# -9V_Supply.net
KiCad netlist of a schematic drawn in Altium Designer
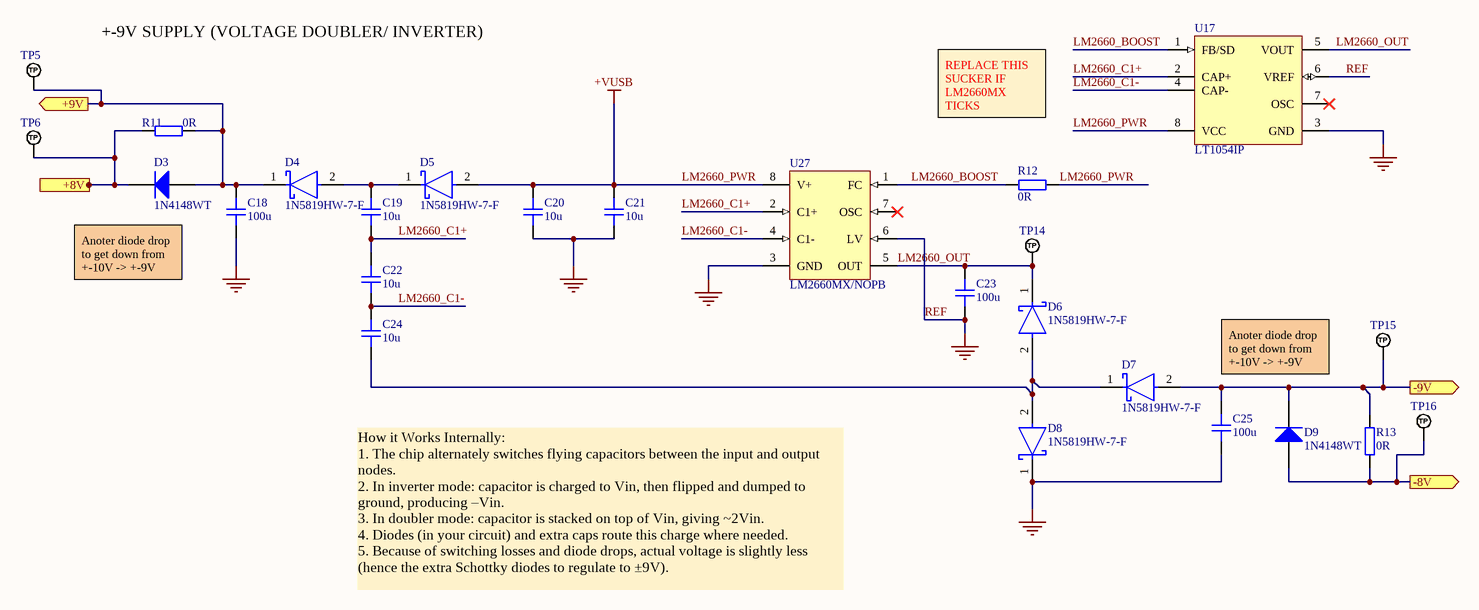
[diagram p0: +-9V Supply.SchDoc]

(export (version "E")
  (design (tool "Eeschema 10.0.6"))
  (components
    (comp (ref "C18")
      (value "100u")
      (footprint "CAP_1210")
      (description "Capacitor SMD 1210")
      (libsource (lib "Schematic-Lib-PhilsLab") (part "CAP_1210"))
    )
    (comp (ref "C19")
      (value "10u")
      (footprint "CAP_1210")
      (description "Capacitor SMD 1210")
      (libsource (lib "Schematic-Lib-PhilsLab") (part "CAP_1210"))
    )
    (comp (ref "C20")
      (value "10u")
      (footprint "CAP_1210")
      (description "Capacitor SMD 1210")
      (libsource (lib "Schematic-Lib-PhilsLab") (part "CAP_1210"))
    )
    (comp (ref "C21")
      (value "10u")
      (footprint "CAP_1210")
      (description "Capacitor SMD 1210")
      (libsource (lib "Schematic-Lib-PhilsLab") (part "CAP_1210"))
    )
    (comp (ref "C22")
      (value "10u")
      (footprint "CAP_1210")
      (description "Capacitor SMD 1210")
      (libsource (lib "Schematic-Lib-PhilsLab") (part "CAP_1210"))
    )
    (comp (ref "C23")
      (value "100u")
      (footprint "CAP_1210")
      (description "Capacitor SMD 1210")
      (libsource (lib "Schematic-Lib-PhilsLab") (part "CAP_1210"))
    )
    (comp (ref "C24")
      (value "10u")
      (footprint "CAP_1210")
      (description "Capacitor SMD 1210")
      (libsource (lib "Schematic-Lib-PhilsLab") (part "CAP_1210"))
    )
    (comp (ref "C25")
      (value "100u")
      (footprint "CAP_1210")
      (description "Capacitor SMD 1210")
      (libsource (lib "Schematic-Lib-PhilsLab") (part "CAP_1210"))
    )
    (comp (ref "D3")
      (value "1N4148WT")
      (footprint "FAIR-SOD-523F-2_V")
      (description "High Conductance Fast Switching Diode, 75 V, -55 to 150 degC, 2-Pin SOD523F, RoHS")
      (fields (field (name "MANUFACTURER") "Fairchild Semiconductor"))
      (libsource (lib "Altium Content Vault") (part "FAIR-D_K1A2-2"))
    )
    (comp (ref "D4")
      (value "1N5819HW-7-F")
      (footprint "FP-SOD123-IPC_A")
      (description "DIODE SCHOTTKY 40V 1A SOD123")
      (libsource (lib "Altium Content Vault") (part "1d6ec82d83fb6aee721767c19dac4b9"))
    )
    (comp (ref "D5")
      (value "1N5819HW-7-F")
      (footprint "FP-SOD123-IPC_A")
      (description "DIODE SCHOTTKY 40V 1A SOD123")
      (libsource (lib "Altium Content Vault") (part "1d6ec82d83fb6aee721767c19dac4b9"))
    )
    (comp (ref "D6")
      (value "1N5819HW-7-F")
      (footprint "FP-SOD123-IPC_A")
      (description "DIODE SCHOTTKY 40V 1A SOD123")
      (libsource (lib "Altium Content Vault") (part "1d6ec82d83fb6aee721767c19dac4b9"))
    )
    (comp (ref "D7")
      (value "1N5819HW-7-F")
      (footprint "FP-SOD123-IPC_A")
      (description "DIODE SCHOTTKY 40V 1A SOD123")
      (libsource (lib "Altium Content Vault") (part "1d6ec82d83fb6aee721767c19dac4b9"))
    )
    (comp (ref "D8")
      (value "1N5819HW-7-F")
      (footprint "FP-SOD123-IPC_A")
      (description "DIODE SCHOTTKY 40V 1A SOD123")
      (libsource (lib "Altium Content Vault") (part "1d6ec82d83fb6aee721767c19dac4b9"))
    )
    (comp (ref "D9")
      (value "1N4148WT")
      (footprint "FAIR-SOD-523F-2_V")
      (description "High Conductance Fast Switching Diode, 75 V, -55 to 150 degC, 2-Pin SOD523F, RoHS")
      (fields (field (name "MANUFACTURER") "Fairchild Semiconductor"))
      (libsource (lib "Altium Content Vault") (part "FAIR-D_K1A2-2"))
    )
    (comp (ref "R11")
      (value "0R")
      (footprint "RES_0603")
      (description "Resistor SMD 0603")
      (libsource (lib "Schematic-Lib-PhilsLab") (part "RES_0603"))
    )
    (comp (ref "R12")
      (value "0R")
      (footprint "RES_0603")
      (description "Resistor SMD 0603")
      (libsource (lib "Schematic-Lib-PhilsLab") (part "RES_0603"))
    )
    (comp (ref "R13")
      (value "0R")
      (footprint "RES_0603")
      (description "Resistor SMD 0603")
      (libsource (lib "Schematic-Lib-PhilsLab") (part "RES_0603"))
    )
    (comp (ref "TP5")
      (value "TP_NOBOM")
      (footprint "PAD_RND_1MM")
      (description "Test Point Round 1mm (NO BOM)")
      (libsource (lib "Schematic-Lib-PhilsLab") (part "TEST_POINT_RND_1MM"))
    )
    (comp (ref "TP6")
      (value "TP_NOBOM")
      (footprint "PAD_RND_1MM")
      (description "Test Point Round 1mm (NO BOM)")
      (libsource (lib "Schematic-Lib-PhilsLab") (part "TEST_POINT_RND_1MM"))
    )
    (comp (ref "TP14")
      (value "TP_NOBOM")
      (footprint "PAD_RND_1MM")
      (description "Test Point Round 1mm (NO BOM)")
      (libsource (lib "Schematic-Lib-PhilsLab") (part "TEST_POINT_RND_1MM"))
    )
    (comp (ref "TP15")
      (value "TP_NOBOM")
      (footprint "PAD_RND_1MM")
      (description "Test Point Round 1mm (NO BOM)")
      (libsource (lib "Schematic-Lib-PhilsLab") (part "TEST_POINT_RND_1MM"))
    )
    (comp (ref "TP16")
      (value "TP_NOBOM")
      (footprint "PAD_RND_1MM")
      (description "Test Point Round 1mm (NO BOM)")
      (libsource (lib "Schematic-Lib-PhilsLab") (part "TEST_POINT_RND_1MM"))
    )
    (comp (ref "U17")
      (value "LT1054IP")
      (footprint "P0008A")
      (fields (field (name "MANUFACTURER") "Texas Instruments"))
      (libsource (lib "Altium Content Vault") (part "TI-1054P8"))
    )
    (comp (ref "U27")
      (value "LM2660MX/NOPB")
      (footprint "D0008A_M")
      (description "Switched Capacitor Voltage Converter, 8-pin Narrow SOIC, Pb-Free")
      (fields (field (name "MANUFACTURER") "Texas Instruments"))
      (libsource (lib "Altium Content Vault") (part "PM-CHP-LM2660M-8"))
    )
  )
  (nets
    (net (code "1") (name "+VUSB") (class "Default")
      (node (ref "C20") (pin "2") (pinfunction "2_2") (pintype "passive"))
      (node (ref "C21") (pin "2") (pinfunction "2_2") (pintype "passive"))
      (node (ref "D5") (pin "2") (pinfunction "A_2") (pintype "passive"))
      (node (ref "R12") (pin "1") (pinfunction "1_1") (pintype "passive"))
      (node (ref "U17") (pin "8") (pinfunction "VCC_8") (pintype "power_in"))
      (node (ref "U27") (pin "8") (pinfunction "V+_8") (pintype "power_in"))
    )
    (net (code "2") (name "/+8V") (class "Default")
      (node (ref "D3") (pin "1") (pinfunction "K_1") (pintype "passive"))
      (node (ref "R11") (pin "1") (pinfunction "1_1") (pintype "passive"))
      (node (ref "TP6") (pin "1") (pinfunction "TP_1") (pintype "passive"))
    )
    (net (code "3") (name "/+9V") (class "Default")
      (node (ref "C18") (pin "2") (pinfunction "2_2") (pintype "passive"))
      (node (ref "D3") (pin "2") (pinfunction "A_2") (pintype "passive"))
      (node (ref "D4") (pin "1") (pinfunction "C_1") (pintype "passive"))
      (node (ref "R11") (pin "2") (pinfunction "2_2") (pintype "passive"))
      (node (ref "TP5") (pin "1") (pinfunction "TP_1") (pintype "passive"))
    )
    (net (code "4") (name "/-8V") (class "Default")
      (node (ref "D9") (pin "2") (pinfunction "A_2") (pintype "passive"))
      (node (ref "R13") (pin "1") (pinfunction "1_1") (pintype "passive"))
      (node (ref "TP16") (pin "1") (pinfunction "TP_1") (pintype "passive"))
    )
    (net (code "5") (name "/-9V") (class "Default")
      (node (ref "C25") (pin "2") (pinfunction "2_2") (pintype "passive"))
      (node (ref "D7") (pin "2") (pinfunction "A_2") (pintype "passive"))
      (node (ref "D9") (pin "1") (pinfunction "K_1") (pintype "passive"))
      (node (ref "R13") (pin "2") (pinfunction "2_2") (pintype "passive"))
      (node (ref "TP15") (pin "1") (pinfunction "TP_1") (pintype "passive"))
    )
    (net (code "6") (name "/LM2660_BOOST") (class "Default")
      (node (ref "R12") (pin "2") (pinfunction "2_2") (pintype "passive"))
      (node (ref "U17") (pin "1") (pinfunction "FB/SD_1") (pintype "input"))
      (node (ref "U27") (pin "1") (pinfunction "FC_1") (pintype "input"))
    )
    (net (code "7") (name "/LM2660_C1+") (class "Default")
      (node (ref "C19") (pin "1") (pinfunction "1_1") (pintype "passive"))
      (node (ref "C22") (pin "2") (pinfunction "2_2") (pintype "passive"))
      (node (ref "U17") (pin "2") (pinfunction "CAP+_2") (pintype "passive"))
      (node (ref "U27") (pin "2") (pinfunction "C1+_2") (pintype "input"))
    )
    (net (code "8") (name "/LM2660_C1-") (class "Default")
      (node (ref "C22") (pin "1") (pinfunction "1_1") (pintype "passive"))
      (node (ref "C24") (pin "2") (pinfunction "2_2") (pintype "passive"))
      (node (ref "U17") (pin "4") (pinfunction "CAP-_4") (pintype "passive"))
      (node (ref "U27") (pin "4") (pinfunction "C1-_4") (pintype "input"))
    )
    (net (code "9") (name "/LM2660_OUT") (class "Default")
      (node (ref "C23") (pin "2") (pinfunction "2_2") (pintype "passive"))
      (node (ref "D6") (pin "1") (pinfunction "C_1") (pintype "passive"))
      (node (ref "TP14") (pin "1") (pinfunction "TP_1") (pintype "passive"))
      (node (ref "U17") (pin "5") (pinfunction "VOUT_5") (pintype "power_in"))
      (node (ref "U27") (pin "5") (pinfunction "OUT_5") (pintype "power_in"))
    )
    (net (code "10") (name "GND") (class "Default")
      (node (ref "C18") (pin "1") (pinfunction "1_1") (pintype "passive"))
      (node (ref "C20") (pin "1") (pinfunction "1_1") (pintype "passive"))
      (node (ref "C21") (pin "1") (pinfunction "1_1") (pintype "passive"))
      (node (ref "C23") (pin "1") (pinfunction "1_1") (pintype "passive"))
      (node (ref "C25") (pin "1") (pinfunction "1_1") (pintype "passive"))
      (node (ref "D8") (pin "1") (pinfunction "C_1") (pintype "passive"))
      (node (ref "U17") (pin "3") (pinfunction "GND_3") (pintype "power_in"))
      (node (ref "U17") (pin "6") (pinfunction "VREF_6") (pintype "bidirectional"))
      (node (ref "U27") (pin "3") (pinfunction "GND_3") (pintype "power_in"))
      (node (ref "U27") (pin "6") (pinfunction "LV_6") (pintype "input"))
    )
    (net (code "11") (name "Net-(D4-A)") (class "Default")
      (node (ref "C19") (pin "2") (pinfunction "2_2") (pintype "passive"))
      (node (ref "D4") (pin "2") (pinfunction "A_2") (pintype "passive"))
      (node (ref "D5") (pin "1") (pinfunction "C_1") (pintype "passive"))
    )
    (net (code "12") (name "Net-(D6-A)") (class "Default")
      (node (ref "C24") (pin "1") (pinfunction "1_1") (pintype "passive"))
      (node (ref "D6") (pin "2") (pinfunction "A_2") (pintype "passive"))
      (node (ref "D7") (pin "1") (pinfunction "C_1") (pintype "passive"))
      (node (ref "D8") (pin "2") (pinfunction "A_2") (pintype "passive"))
    )
    (net (code "13") (name "unconnected-(U17-OSC-Pad7)") (class "Default")
      (node (ref "U17") (pin "7") (pinfunction "OSC_7") (pintype "passive+no_connect"))
    )
    (net (code "14") (name "unconnected-(U27-OSC-Pad7)") (class "Default")
      (node (ref "U27") (pin "7") (pinfunction "OSC_7") (pintype "input+no_connect"))
    )
  )
)
